# startStop.net
KiCad netlist of a schematic drawn in Altium Designer
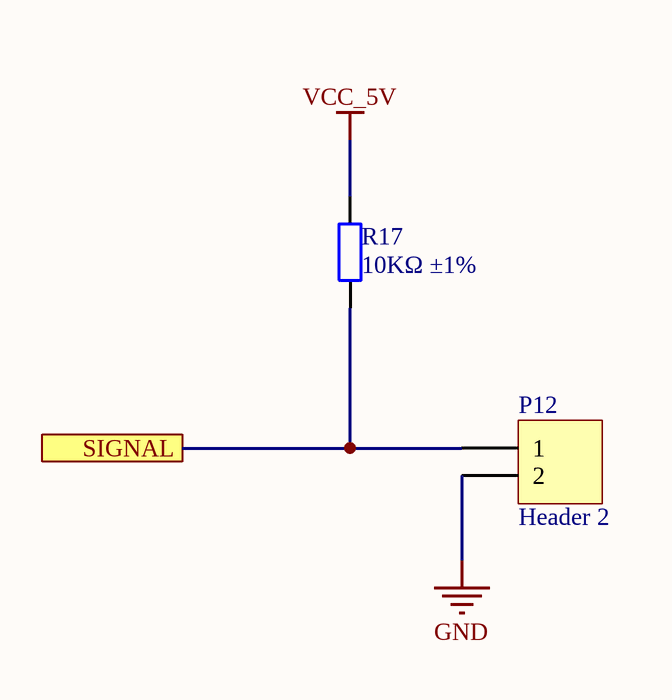
[diagram p0: startStop.SchDoc]

(export (version "E")
  (design (tool "Eeschema 10.0.6"))
  (components
    (comp (ref "P12")
      (value "Header 2")
      (footprint "HDR1X2")
      (description "Header, 2-Pin")
      (fields (field (name "PUBLISHER") "Altium Limited"))
      (libsource (lib "Miscellaneous Connectors") (part "Header 2"))
    )
    (comp (ref "R17")
      (value "10KΩ ±1%")
      (footprint "0603_R")
      (description "Chip resistor")
      (fields (field (name "MANUFACTURER") "Uniroyal Elec") (field (name "PARTNUMBER") "0603WAF1002T5E"))
      (libsource (lib "RES") (part "0603 10K (1002) 1%"))
    )
  )
  (nets
    (net (code "1") (name "/SIGNAL") (class "Default")
      (node (ref "P12") (pin "1") (pinfunction "1_1") (pintype "passive"))
      (node (ref "R17") (pin "1") (pinfunction "1_1") (pintype "passive"))
    )
    (net (code "2") (name "GND") (class "Default")
      (node (ref "P12") (pin "2") (pinfunction "2_2") (pintype "passive"))
    )
    (net (code "3") (name "VCC_5V") (class "Default")
      (node (ref "R17") (pin "2") (pinfunction "2_2") (pintype "passive"))
    )
  )
)
